# Battery-Charger-Prototype.net
KiCad netlist of a schematic drawn in EAGLE
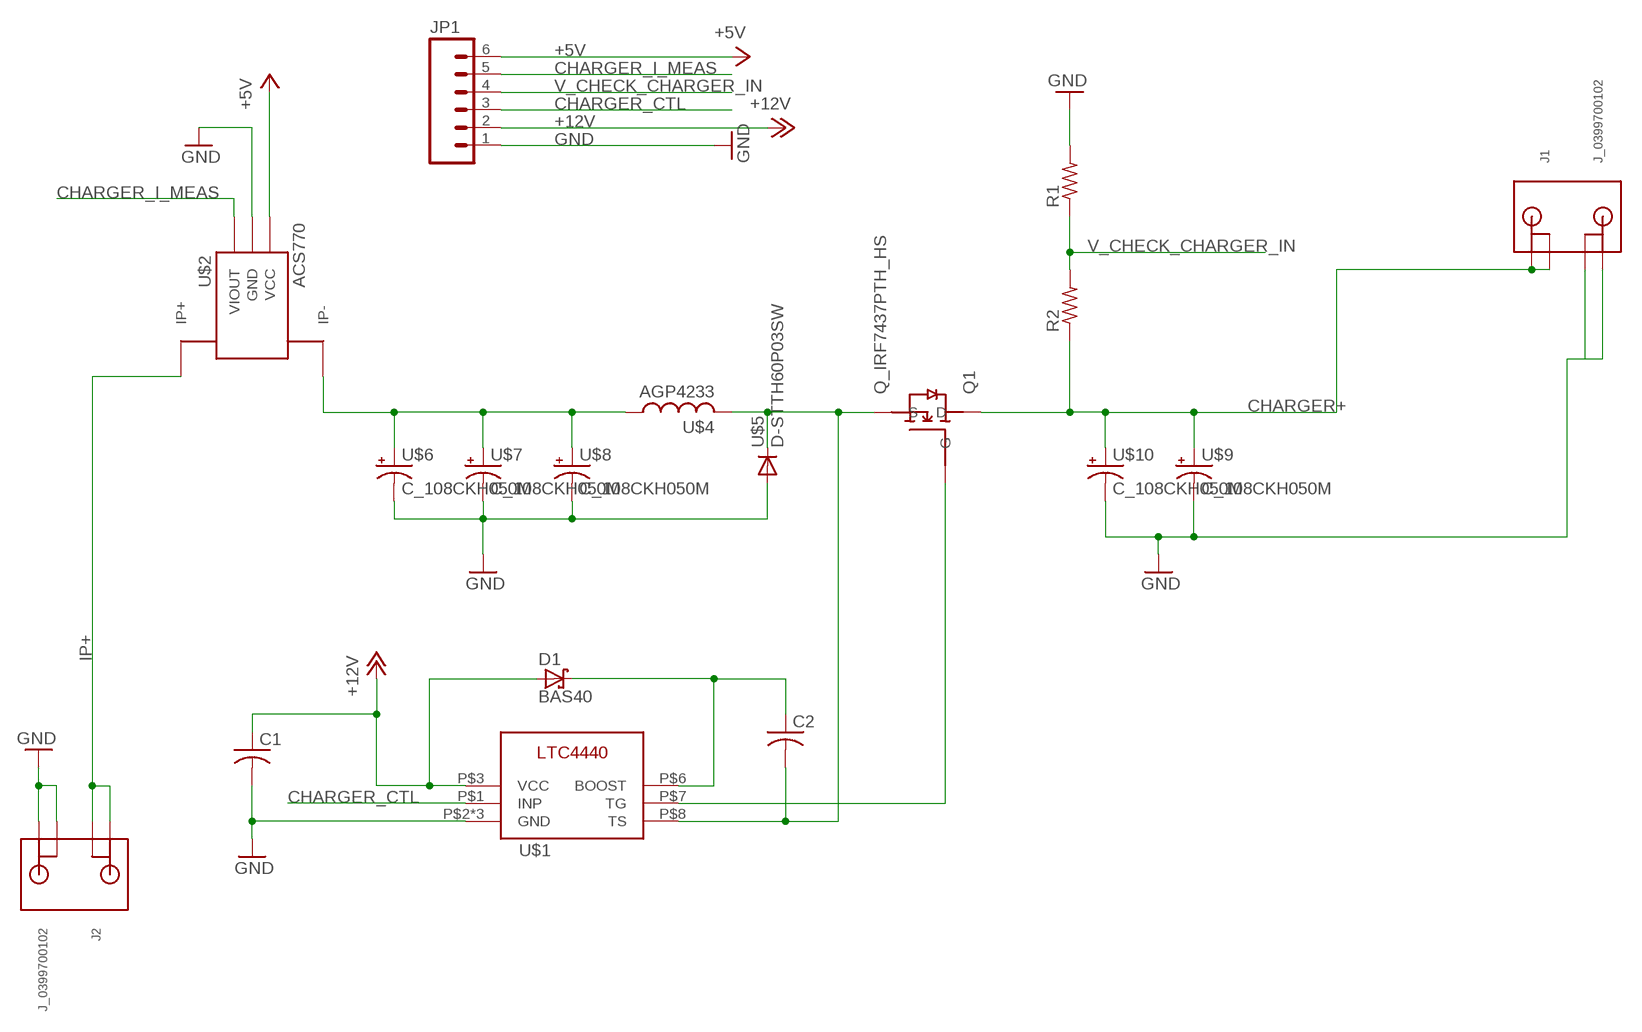
[diagram p0: schematic, sheet 1]

(export (version "E")
  (design (tool "Eeschema 10.0.6"))
  (components
    (comp (ref "C1")
      (value "C-USC1206")
      (footprint "eagle-import:C1206")
      (libsource (lib "eagle-import") (part "C-USC1206"))
    )
    (comp (ref "C2")
      (value "C-USC1206")
      (footprint "eagle-import:C1206")
      (libsource (lib "eagle-import") (part "C-USC1206"))
    )
    (comp (ref "D1")
      (value "BAS40")
      (footprint "eagle-import:SOT23")
      (libsource (lib "eagle-import") (part "BAS40"))
    )
    (comp (ref "J1")
      (value "J_0399700102")
      (footprint "eagle-import:J_2CONHC")
      (libsource (lib "eagle-import") (part "J_0399700102"))
    )
    (comp (ref "J2")
      (value "J_0399700102")
      (footprint "eagle-import:J_2CONHC")
      (libsource (lib "eagle-import") (part "J_0399700102"))
    )
    (comp (ref "JP1")
      (value "M06SILK_FEMALE_PTH")
      (footprint "eagle-import:1X06")
      (libsource (lib "eagle-import") (part "M06SILK_FEMALE_PTH"))
    )
    (comp (ref "Q1")
      (value "Q_IRF7437PTH_HS")
      (footprint "eagle-import:TO-220-531102B02500G")
      (libsource (lib "eagle-import") (part "Q_IRF7437PTH_HS"))
    )
    (comp (ref "R1")
      (value "R-US_R1206")
      (footprint "eagle-import:R1206")
      (libsource (lib "eagle-import") (part "R-US_R1206"))
    )
    (comp (ref "R2")
      (value "R-US_R1206")
      (footprint "eagle-import:R1206")
      (libsource (lib "eagle-import") (part "R-US_R1206"))
    )
    (comp (ref "U$1")
      (value "LTC4440")
      (footprint "eagle-import:MS8E")
      (libsource (lib "eagle-import") (part "LTC4440"))
    )
    (comp (ref "U$2")
      (value "ACS770")
      (footprint "eagle-import:PFF_LEADFORM")
      (libsource (lib "eagle-import") (part "ACS770"))
    )
    (comp (ref "U$4")
      (value "AGP4233")
      (footprint "eagle-import:AGP4233")
      (libsource (lib "eagle-import") (part "AGP4233"))
    )
    (comp (ref "U$5")
      (value "D-STTH60P03SW")
      (footprint "eagle-import:TO-247-VERT")
      (libsource (lib "eagle-import") (part "D-STTH60P03SW"))
    )
    (comp (ref "U$6")
      (value "C_108CKH050M")
      (footprint "eagle-import:C_16MM")
      (libsource (lib "eagle-import") (part "C_108CKH050M"))
    )
    (comp (ref "U$7")
      (value "C_108CKH050M")
      (footprint "eagle-import:C_16MM")
      (libsource (lib "eagle-import") (part "C_108CKH050M"))
    )
    (comp (ref "U$8")
      (value "C_108CKH050M")
      (footprint "eagle-import:C_16MM")
      (libsource (lib "eagle-import") (part "C_108CKH050M"))
    )
    (comp (ref "U$9")
      (value "C_108CKH050M")
      (footprint "eagle-import:C_16MM")
      (libsource (lib "eagle-import") (part "C_108CKH050M"))
    )
    (comp (ref "U$10")
      (value "C_108CKH050M")
      (footprint "eagle-import:C_16MM")
      (libsource (lib "eagle-import") (part "C_108CKH050M"))
    )
  )
  (nets
    (net (code "1") (name "+5V") (class "Default")
      (node (ref "JP1") (pin "6") (pinfunction "6_6") (pintype "passive"))
      (node (ref "U$2") (pin "1") (pinfunction "VCC_1") (pintype "bidirectional"))
    )
    (net (code "2") (name "+12V") (class "Default")
      (node (ref "C1") (pin "1") (pinfunction "1_1") (pintype "passive"))
      (node (ref "D1") (pin "1") (pinfunction "A_1") (pintype "passive"))
      (node (ref "JP1") (pin "2") (pinfunction "2_2") (pintype "passive"))
      (node (ref "U$1") (pin "P$3") (pinfunction "VCC_P$3") (pintype "bidirectional"))
    )
    (net (code "3") (name "/CHARGER+") (class "Default")
      (node (ref "J1") (pin "PIN1-1") (pinfunction "1-1_PIN1-1") (pintype "bidirectional"))
      (node (ref "J1") (pin "PIN1-2") (pinfunction "1-2_PIN1-2") (pintype "bidirectional"))
      (node (ref "Q1") (pin "2") (pinfunction "D_2") (pintype "bidirectional"))
      (node (ref "R2") (pin "1") (pinfunction "1_1") (pintype "passive"))
      (node (ref "U$10") (pin "+") (pinfunction "+_+") (pintype "passive"))
      (node (ref "U$9") (pin "+") (pinfunction "+_+") (pintype "passive"))
    )
    (net (code "4") (name "/CHARGER_CTL") (class "Default")
      (node (ref "JP1") (pin "3") (pinfunction "3_3") (pintype "passive"))
      (node (ref "U$1") (pin "P$1") (pinfunction "INP_P$1") (pintype "bidirectional"))
    )
    (net (code "5") (name "/CHARGER_I_MEAS") (class "Default")
      (node (ref "JP1") (pin "5") (pinfunction "5_5") (pintype "passive"))
      (node (ref "U$2") (pin "3") (pinfunction "VIOUT_3") (pintype "bidirectional"))
    )
    (net (code "6") (name "/IP+") (class "Default")
      (node (ref "J2") (pin "PIN1-1") (pinfunction "1-1_PIN1-1") (pintype "bidirectional"))
      (node (ref "J2") (pin "PIN1-2") (pinfunction "1-2_PIN1-2") (pintype "bidirectional"))
      (node (ref "U$2") (pin "4_1") (pinfunction "IP+_4_1") (pintype "bidirectional"))
      (node (ref "U$2") (pin "4_10") (pinfunction "IP+_4_10") (pintype "bidirectional"))
      (node (ref "U$2") (pin "4_11") (pinfunction "IP+_4_11") (pintype "bidirectional"))
      (node (ref "U$2") (pin "4_12") (pinfunction "IP+_4_12") (pintype "bidirectional"))
      (node (ref "U$2") (pin "4_13") (pinfunction "IP+_4_13") (pintype "bidirectional"))
      (node (ref "U$2") (pin "4_14") (pinfunction "IP+_4_14") (pintype "bidirectional"))
      (node (ref "U$2") (pin "4_15") (pinfunction "IP+_4_15") (pintype "bidirectional"))
      (node (ref "U$2") (pin "4_16") (pinfunction "IP+_4_16") (pintype "bidirectional"))
      (node (ref "U$2") (pin "4_2") (pinfunction "IP+_4_2") (pintype "bidirectional"))
      (node (ref "U$2") (pin "4_3") (pinfunction "IP+_4_3") (pintype "bidirectional"))
      (node (ref "U$2") (pin "4_4") (pinfunction "IP+_4_4") (pintype "bidirectional"))
      (node (ref "U$2") (pin "4_5") (pinfunction "IP+_4_5") (pintype "bidirectional"))
      (node (ref "U$2") (pin "4_6") (pinfunction "IP+_4_6") (pintype "bidirectional"))
      (node (ref "U$2") (pin "4_7") (pinfunction "IP+_4_7") (pintype "bidirectional"))
      (node (ref "U$2") (pin "4_8") (pinfunction "IP+_4_8") (pintype "bidirectional"))
      (node (ref "U$2") (pin "4_9") (pinfunction "IP+_4_9") (pintype "bidirectional"))
      (node (ref "U$2") (pin "4_B") (pinfunction "IP+_4_B") (pintype "bidirectional"))
      (node (ref "U$2") (pin "4_T") (pinfunction "IP+_4_T") (pintype "bidirectional"))
    )
    (net (code "7") (name "/V_CHECK_CHARGER_IN") (class "Default")
      (node (ref "JP1") (pin "4") (pinfunction "4_4") (pintype "passive"))
      (node (ref "R1") (pin "1") (pinfunction "1_1") (pintype "passive"))
      (node (ref "R2") (pin "2") (pinfunction "2_2") (pintype "passive"))
    )
    (net (code "8") (name "GND") (class "Default")
      (node (ref "C1") (pin "2") (pinfunction "2_2") (pintype "passive"))
      (node (ref "J1") (pin "PIN2-1") (pinfunction "2-1_PIN2-1") (pintype "bidirectional"))
      (node (ref "J1") (pin "PIN2-2") (pinfunction "2-2_PIN2-2") (pintype "bidirectional"))
      (node (ref "J2") (pin "PIN2-1") (pinfunction "2-1_PIN2-1") (pintype "bidirectional"))
      (node (ref "J2") (pin "PIN2-2") (pinfunction "2-2_PIN2-2") (pintype "bidirectional"))
      (node (ref "JP1") (pin "1") (pinfunction "1_1") (pintype "passive"))
      (node (ref "R1") (pin "2") (pinfunction "2_2") (pintype "passive"))
      (node (ref "U$1") (pin "P$2") (pinfunction "GND_P$2") (pintype "bidirectional"))
      (node (ref "U$1") (pin "P$4") (pinfunction "GND_P$4") (pintype "bidirectional"))
      (node (ref "U$1") (pin "P$9") (pinfunction "GND_P$9") (pintype "bidirectional"))
      (node (ref "U$10") (pin "GND") (pinfunction "-_GND") (pintype "passive"))
      (node (ref "U$2") (pin "2") (pinfunction "GND_2") (pintype "bidirectional"))
      (node (ref "U$5") (pin "P$1") (pinfunction "A_P$1") (pintype "passive"))
      (node (ref "U$5") (pin "P$3") (pinfunction "A_P$3") (pintype "passive"))
      (node (ref "U$6") (pin "GND") (pinfunction "-_GND") (pintype "passive"))
      (node (ref "U$7") (pin "GND") (pinfunction "-_GND") (pintype "passive"))
      (node (ref "U$8") (pin "GND") (pinfunction "-_GND") (pintype "passive"))
      (node (ref "U$9") (pin "GND") (pinfunction "-_GND") (pintype "passive"))
    )
    (net (code "9") (name "Net-(D1-C)") (class "Default")
      (node (ref "C2") (pin "1") (pinfunction "1_1") (pintype "passive"))
      (node (ref "D1") (pin "3") (pinfunction "C_3") (pintype "passive"))
      (node (ref "U$1") (pin "P$6") (pinfunction "BOOST_P$6") (pintype "bidirectional"))
    )
    (net (code "10") (name "Net-(Q1-G)") (class "Default")
      (node (ref "Q1") (pin "1") (pinfunction "G_1") (pintype "bidirectional"))
      (node (ref "U$1") (pin "P$7") (pinfunction "TG_P$7") (pintype "bidirectional"))
    )
    (net (code "11") (name "Net-(Q1-S)") (class "Default")
      (node (ref "C2") (pin "2") (pinfunction "2_2") (pintype "passive"))
      (node (ref "Q1") (pin "3") (pinfunction "S_3") (pintype "bidirectional"))
      (node (ref "U$1") (pin "P$8") (pinfunction "TS_P$8") (pintype "bidirectional"))
      (node (ref "U$4") (pin "P$2") (pinfunction "2_P$2") (pintype "passive"))
      (node (ref "U$5") (pin "P$2") (pinfunction "C_P$2") (pintype "passive"))
    )
    (net (code "12") (name "Net-(U$4-1)") (class "Default")
      (node (ref "U$2") (pin "5_1") (pinfunction "IP-_5_1") (pintype "bidirectional"))
      (node (ref "U$2") (pin "5_10") (pinfunction "IP-_5_10") (pintype "bidirectional"))
      (node (ref "U$2") (pin "5_11") (pinfunction "IP-_5_11") (pintype "bidirectional"))
      (node (ref "U$2") (pin "5_12") (pinfunction "IP-_5_12") (pintype "bidirectional"))
      (node (ref "U$2") (pin "5_13") (pinfunction "IP-_5_13") (pintype "bidirectional"))
      (node (ref "U$2") (pin "5_14") (pinfunction "IP-_5_14") (pintype "bidirectional"))
      (node (ref "U$2") (pin "5_15") (pinfunction "IP-_5_15") (pintype "bidirectional"))
      (node (ref "U$2") (pin "5_16") (pinfunction "IP-_5_16") (pintype "bidirectional"))
      (node (ref "U$2") (pin "5_2") (pinfunction "IP-_5_2") (pintype "bidirectional"))
      (node (ref "U$2") (pin "5_3") (pinfunction "IP-_5_3") (pintype "bidirectional"))
      (node (ref "U$2") (pin "5_4") (pinfunction "IP-_5_4") (pintype "bidirectional"))
      (node (ref "U$2") (pin "5_5") (pinfunction "IP-_5_5") (pintype "bidirectional"))
      (node (ref "U$2") (pin "5_6") (pinfunction "IP-_5_6") (pintype "bidirectional"))
      (node (ref "U$2") (pin "5_7") (pinfunction "IP-_5_7") (pintype "bidirectional"))
      (node (ref "U$2") (pin "5_8") (pinfunction "IP-_5_8") (pintype "bidirectional"))
      (node (ref "U$2") (pin "5_9") (pinfunction "IP-_5_9") (pintype "bidirectional"))
      (node (ref "U$2") (pin "5_B") (pinfunction "IP-_5_B") (pintype "bidirectional"))
      (node (ref "U$2") (pin "5_T") (pinfunction "IP-_5_T") (pintype "bidirectional"))
      (node (ref "U$4") (pin "P$1") (pinfunction "1_P$1") (pintype "passive"))
      (node (ref "U$6") (pin "+") (pinfunction "+_+") (pintype "passive"))
      (node (ref "U$7") (pin "+") (pinfunction "+_+") (pintype "passive"))
      (node (ref "U$8") (pin "+") (pinfunction "+_+") (pintype "passive"))
    )
  )
)
